# Temperature_Sensor.net
KiCad netlist of a schematic drawn in Altium Designer
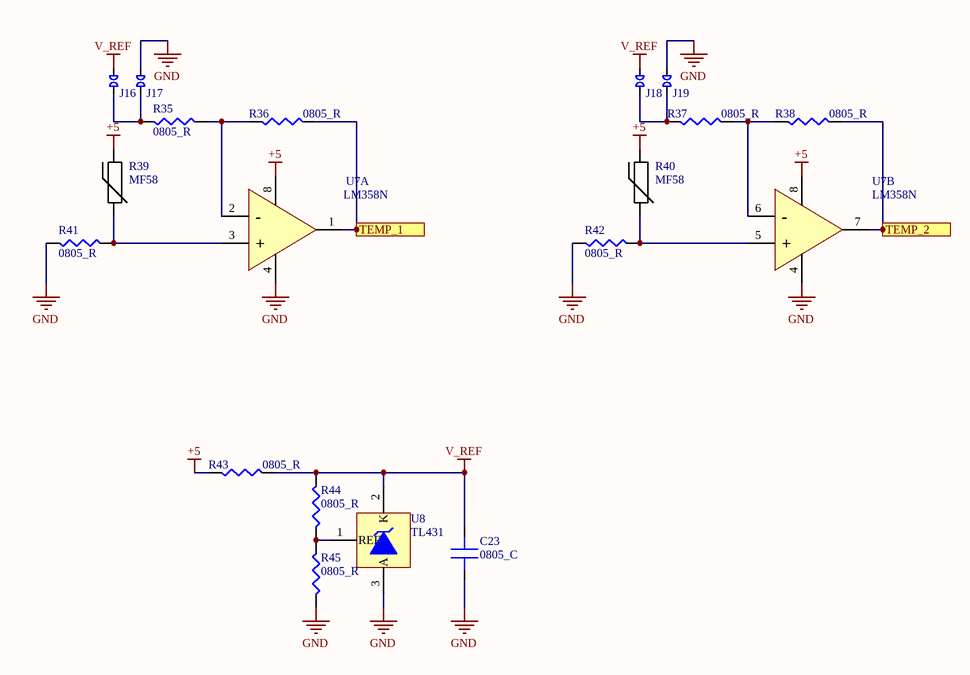
[diagram p0: Temperature Sensor.SchDoc]

(export (version "E")
  (design (tool "Eeschema 10.0.6"))
  (components
    (comp (ref "C23")
      (value "0805_C")
      (footprint "C0805 - 0.1uf")
      (description "0805 Capacitor")
      (libsource (lib "TimerSMD_Components") (part "0805 Capacitor"))
    )
    (comp (ref "J16")
      (value "Jumper Pads")
      (footprint "JMP")
      (libsource (lib "TimerSMD_Components") (part "Jumper Pads"))
    )
    (comp (ref "J17")
      (value "Jumper Pads")
      (footprint "JMP")
      (libsource (lib "TimerSMD_Components") (part "Jumper Pads"))
    )
    (comp (ref "J18")
      (value "Jumper Pads")
      (footprint "JMP")
      (libsource (lib "TimerSMD_Components") (part "Jumper Pads"))
    )
    (comp (ref "J19")
      (value "Jumper Pads")
      (footprint "JMP")
      (libsource (lib "TimerSMD_Components") (part "Jumper Pads"))
    )
    (comp (ref "R35")
      (value "0805_R")
      (footprint "R0805")
      (libsource (lib "TimerSMD_Components") (part "0805 Resistor"))
    )
    (comp (ref "R36")
      (value "0805_R")
      (footprint "R0805")
      (libsource (lib "TimerSMD_Components") (part "0805 Resistor"))
    )
    (comp (ref "R37")
      (value "0805_R")
      (footprint "R0805")
      (libsource (lib "TimerSMD_Components") (part "0805 Resistor"))
    )
    (comp (ref "R38")
      (value "0805_R")
      (footprint "R0805")
      (libsource (lib "TimerSMD_Components") (part "0805 Resistor"))
    )
    (comp (ref "R39")
      (value "MF58")
      (footprint "NTC 3mm")
      (description "NTC 100K THERMISTOR MF58")
      (libsource (lib "CAD_Symbols") (part "MF58"))
    )
    (comp (ref "R40")
      (value "MF58")
      (footprint "NTC 3mm")
      (description "NTC 100K THERMISTOR MF58")
      (libsource (lib "CAD_Symbols") (part "MF58"))
    )
    (comp (ref "R41")
      (value "0805_R")
      (footprint "R0805")
      (libsource (lib "TimerSMD_Components") (part "0805 Resistor"))
    )
    (comp (ref "R42")
      (value "0805_R")
      (footprint "R0805")
      (libsource (lib "TimerSMD_Components") (part "0805 Resistor"))
    )
    (comp (ref "R43")
      (value "0805_R")
      (footprint "R0805")
      (libsource (lib "TimerSMD_Components") (part "0805 Resistor"))
    )
    (comp (ref "R44")
      (value "0805_R")
      (footprint "R0805")
      (libsource (lib "TimerSMD_Components") (part "0805 Resistor"))
    )
    (comp (ref "R45")
      (value "0805_R")
      (footprint "R0805")
      (libsource (lib "TimerSMD_Components") (part "0805 Resistor"))
    )
    (comp (ref "U7") (value "LM358N") (footprint "SOP8") (libsource (lib "EV_Symbols") (part "LM358N")))
    (comp (ref "U8")
      (value "TL431")
      (footprint "SO-23")
      (description "SMD Voltage References SOT-23")
      (libsource (lib "TimerSMD_Components") (part "TL431"))
    )
  )
  (nets
    (net (code "1") (name "+5") (class "Default")
      (node (ref "R39") (pin "2") (pinfunction "2_2") (pintype "passive"))
      (node (ref "R40") (pin "2") (pinfunction "2_2") (pintype "passive"))
      (node (ref "R43") (pin "2") (pinfunction "2_2") (pintype "passive"))
      (node (ref "U7") (pin "8") (pinfunction "VCC_8") (pintype "passive"))
    )
    (net (code "2") (name "/TEMP_1") (class "Default")
      (node (ref "R36") (pin "1") (pinfunction "1_1") (pintype "passive"))
      (node (ref "U7") (pin "1") (pinfunction "OUT1_1") (pintype "passive"))
    )
    (net (code "3") (name "/TEMP_2") (class "Default")
      (node (ref "R38") (pin "1") (pinfunction "1_1") (pintype "passive"))
      (node (ref "U7") (pin "7") (pinfunction "OUT1_7") (pintype "passive"))
    )
    (net (code "4") (name "GND") (class "Default")
      (node (ref "C23") (pin "1") (pinfunction "1_1") (pintype "passive"))
      (node (ref "J17") (pin "2") (pinfunction "2_2") (pintype "passive"))
      (node (ref "J19") (pin "2") (pinfunction "2_2") (pintype "passive"))
      (node (ref "R41") (pin "1") (pinfunction "1_1") (pintype "passive"))
      (node (ref "R42") (pin "1") (pinfunction "1_1") (pintype "passive"))
      (node (ref "R45") (pin "2") (pinfunction "2_2") (pintype "passive"))
      (node (ref "U7") (pin "4") (pinfunction "VSS_4") (pintype "passive"))
      (node (ref "U8") (pin "3") (pinfunction "A_3") (pintype "passive"))
    )
    (net (code "5") (name "Net-(J16-Pad1)") (class "Default")
      (node (ref "J16") (pin "1") (pinfunction "1_1") (pintype "passive"))
      (node (ref "J17") (pin "1") (pinfunction "1_1") (pintype "passive"))
      (node (ref "R35") (pin "1") (pinfunction "1_1") (pintype "passive"))
    )
    (net (code "6") (name "Net-(J18-Pad1)") (class "Default")
      (node (ref "J18") (pin "1") (pinfunction "1_1") (pintype "passive"))
      (node (ref "J19") (pin "1") (pinfunction "1_1") (pintype "passive"))
      (node (ref "R37") (pin "2") (pinfunction "2_2") (pintype "passive"))
    )
    (net (code "7") (name "Net-(U7A-+)") (class "Default")
      (node (ref "R39") (pin "1") (pinfunction "1_1") (pintype "passive"))
      (node (ref "R41") (pin "2") (pinfunction "2_2") (pintype "passive"))
      (node (ref "U7") (pin "3") (pinfunction "+_3") (pintype "passive"))
    )
    (net (code "8") (name "Net-(U7A--)") (class "Default")
      (node (ref "R35") (pin "2") (pinfunction "2_2") (pintype "passive"))
      (node (ref "R36") (pin "2") (pinfunction "2_2") (pintype "passive"))
      (node (ref "U7") (pin "2") (pinfunction "-_2") (pintype "passive"))
    )
    (net (code "9") (name "Net-(U7B-+)") (class "Default")
      (node (ref "R40") (pin "1") (pinfunction "1_1") (pintype "passive"))
      (node (ref "R42") (pin "2") (pinfunction "2_2") (pintype "passive"))
      (node (ref "U7") (pin "5") (pinfunction "+_5") (pintype "passive"))
    )
    (net (code "10") (name "Net-(U7B--)") (class "Default")
      (node (ref "R37") (pin "1") (pinfunction "1_1") (pintype "passive"))
      (node (ref "R38") (pin "2") (pinfunction "2_2") (pintype "passive"))
      (node (ref "U7") (pin "6") (pinfunction "-_6") (pintype "passive"))
    )
    (net (code "11") (name "Net-(U8-REF)") (class "Default")
      (node (ref "R44") (pin "2") (pinfunction "2_2") (pintype "passive"))
      (node (ref "R45") (pin "1") (pinfunction "1_1") (pintype "passive"))
      (node (ref "U8") (pin "1") (pinfunction "REF_1") (pintype "passive"))
    )
    (net (code "12") (name "V_REF") (class "Default")
      (node (ref "C23") (pin "2") (pinfunction "2_2") (pintype "passive"))
      (node (ref "J16") (pin "2") (pinfunction "2_2") (pintype "passive"))
      (node (ref "J18") (pin "2") (pinfunction "2_2") (pintype "passive"))
      (node (ref "R43") (pin "1") (pinfunction "1_1") (pintype "passive"))
      (node (ref "R44") (pin "1") (pinfunction "1_1") (pintype "passive"))
      (node (ref "U8") (pin "2") (pinfunction "K_2") (pintype "passive"))
    )
  )
)
